# mitosis.net
KiCad netlist of a schematic drawn in Altium Designer
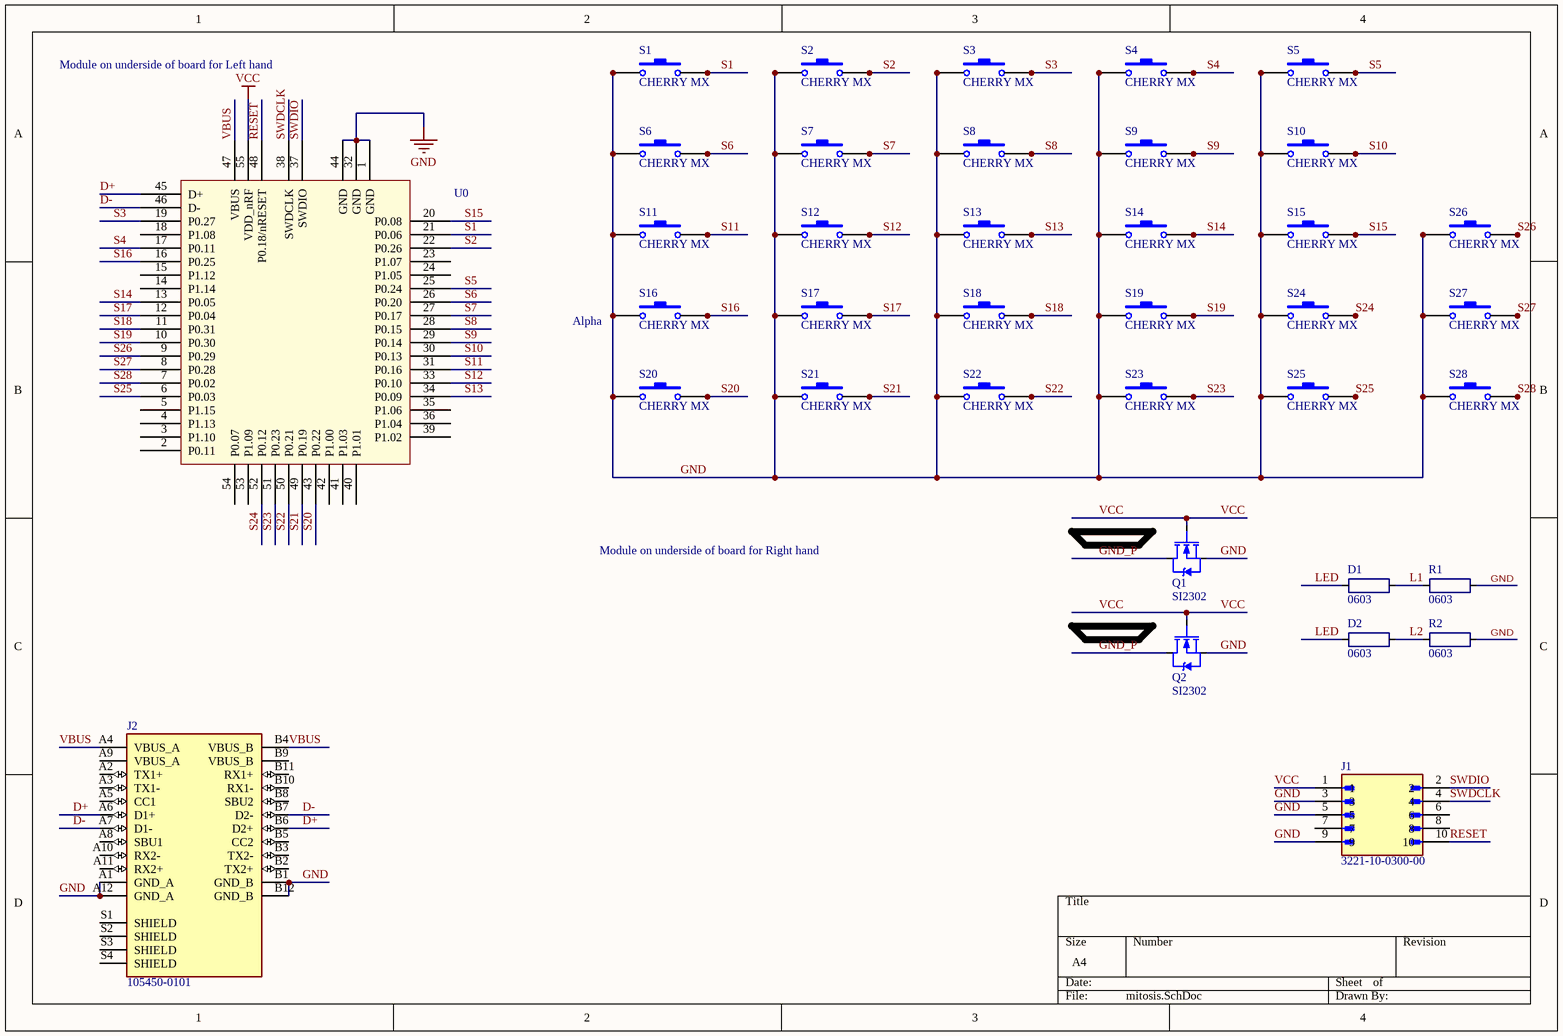
[diagram p0: mitosis.SchDoc]

(export (version "E")
  (design (tool "Eeschema 10.0.6"))
  (components
    (comp (ref "D1") (value "0603") (footprint "RESC2012X06N") (libsource (lib "SK") (part "0603")))
    (comp (ref "D2") (value "0603") (footprint "RESC2012X06N") (libsource (lib "SK") (part "0603")))
    (comp (ref "J1")
      (value "3221-10-0300-00")
      (footprint "mitosis:CNC_3221-10-0300-00")
      (description "Conn Shrouded Header HDR 10 POS 1.27mm Solder ST SMD T/R")
      (fields (field (name "MF") "CNC Tech") (field (name "MANUFACTURER PART NUMBER") "3221-10-0300-00-TR"))
      (libsource (lib "mitosis") (part "3221-10-0300-00"))
    )
    (comp (ref "J2")
      (value "105450-0101")
      (footprint "mitosis:MOLEX_105450-0101")
      (description "Conn USB 3.1 Type C F 24 POS Solder RA SMD 24 Terminal 1 Port USB 3.1 T/R")
      (fields (field (name "MANUFACTURER") "Molex"))
      (libsource (lib "mitosis") (part "105450-0101"))
    )
    (comp (ref "Q1")
      (value "SI2302")
      (footprint "SOT-23")
      (description "N-Channel Logic MOSFET")
      (fields (field (name "PUBLISHER") "Altium Limited"))
      (libsource (lib "SK") (part "SI2302"))
    )
    (comp (ref "Q2")
      (value "SI2302")
      (footprint "SOT-23")
      (description "N-Channel Logic MOSFET")
      (fields (field (name "PUBLISHER") "Altium Limited"))
      (libsource (lib "SK") (part "SI2302"))
    )
    (comp (ref "R1") (value "0603") (footprint "RESC2012X06N") (libsource (lib "SK") (part "0603")))
    (comp (ref "R2") (value "0603") (footprint "RESC2012X06N") (libsource (lib "SK") (part "0603")))
    (comp (ref "S1")
      (value "CHERRY MX")
      (footprint "cherry")
      (description "Switch")
      (fields (field (name "PUBLISHER") "Altium Limited"))
      (libsource (lib "SK") (part "CHERRY MX"))
    )
    (comp (ref "S2")
      (value "CHERRY MX")
      (footprint "cherry")
      (description "Switch")
      (fields (field (name "PUBLISHER") "Altium Limited"))
      (libsource (lib "SK") (part "CHERRY MX"))
    )
    (comp (ref "S3")
      (value "CHERRY MX")
      (footprint "cherry")
      (description "Switch")
      (fields (field (name "PUBLISHER") "Altium Limited"))
      (libsource (lib "SK") (part "CHERRY MX"))
    )
    (comp (ref "S4")
      (value "CHERRY MX")
      (footprint "cherry")
      (description "Switch")
      (fields (field (name "PUBLISHER") "Altium Limited"))
      (libsource (lib "SK") (part "CHERRY MX"))
    )
    (comp (ref "S5")
      (value "CHERRY MX")
      (footprint "cherry")
      (description "Switch")
      (fields (field (name "PUBLISHER") "Altium Limited"))
      (libsource (lib "SK") (part "CHERRY MX"))
    )
    (comp (ref "S6")
      (value "CHERRY MX")
      (footprint "cherry")
      (description "Switch")
      (fields (field (name "PUBLISHER") "Altium Limited"))
      (libsource (lib "SK") (part "CHERRY MX"))
    )
    (comp (ref "S7")
      (value "CHERRY MX")
      (footprint "cherry")
      (description "Switch")
      (fields (field (name "PUBLISHER") "Altium Limited"))
      (libsource (lib "SK") (part "CHERRY MX"))
    )
    (comp (ref "S8")
      (value "CHERRY MX")
      (footprint "cherry")
      (description "Switch")
      (fields (field (name "PUBLISHER") "Altium Limited"))
      (libsource (lib "SK") (part "CHERRY MX"))
    )
    (comp (ref "S9")
      (value "CHERRY MX")
      (footprint "cherry")
      (description "Switch")
      (fields (field (name "PUBLISHER") "Altium Limited"))
      (libsource (lib "SK") (part "CHERRY MX"))
    )
    (comp (ref "S10")
      (value "CHERRY MX")
      (footprint "cherry")
      (description "Switch")
      (fields (field (name "PUBLISHER") "Altium Limited"))
      (libsource (lib "SK") (part "CHERRY MX"))
    )
    (comp (ref "S11")
      (value "CHERRY MX")
      (footprint "cherry")
      (description "Switch")
      (fields (field (name "PUBLISHER") "Altium Limited"))
      (libsource (lib "SK") (part "CHERRY MX"))
    )
    (comp (ref "S12")
      (value "CHERRY MX")
      (footprint "cherry")
      (description "Switch")
      (fields (field (name "PUBLISHER") "Altium Limited"))
      (libsource (lib "SK") (part "CHERRY MX"))
    )
    (comp (ref "S13")
      (value "CHERRY MX")
      (footprint "cherry")
      (description "Switch")
      (fields (field (name "PUBLISHER") "Altium Limited"))
      (libsource (lib "SK") (part "CHERRY MX"))
    )
    (comp (ref "S14")
      (value "CHERRY MX")
      (footprint "cherry")
      (description "Switch")
      (fields (field (name "PUBLISHER") "Altium Limited"))
      (libsource (lib "SK") (part "CHERRY MX"))
    )
    (comp (ref "S15")
      (value "CHERRY MX")
      (footprint "cherry")
      (description "Switch")
      (fields (field (name "PUBLISHER") "Altium Limited"))
      (libsource (lib "SK") (part "CHERRY MX"))
    )
    (comp (ref "S16")
      (value "CHERRY MX")
      (footprint "cherry")
      (description "Switch")
      (fields (field (name "PUBLISHER") "Altium Limited"))
      (libsource (lib "SK") (part "CHERRY MX"))
    )
    (comp (ref "S17")
      (value "CHERRY MX")
      (footprint "cherry")
      (description "Switch")
      (fields (field (name "PUBLISHER") "Altium Limited"))
      (libsource (lib "SK") (part "CHERRY MX"))
    )
    (comp (ref "S18")
      (value "CHERRY MX")
      (footprint "cherry")
      (description "Switch")
      (fields (field (name "PUBLISHER") "Altium Limited"))
      (libsource (lib "SK") (part "CHERRY MX"))
    )
    (comp (ref "S19")
      (value "CHERRY MX")
      (footprint "cherry")
      (description "Switch")
      (fields (field (name "PUBLISHER") "Altium Limited"))
      (libsource (lib "SK") (part "CHERRY MX"))
    )
    (comp (ref "S20")
      (value "CHERRY MX")
      (footprint "cherry")
      (description "Switch")
      (fields (field (name "PUBLISHER") "Altium Limited"))
      (libsource (lib "SK") (part "CHERRY MX"))
    )
    (comp (ref "S21")
      (value "CHERRY MX")
      (footprint "cherry")
      (description "Switch")
      (fields (field (name "PUBLISHER") "Altium Limited"))
      (libsource (lib "SK") (part "CHERRY MX"))
    )
    (comp (ref "S22")
      (value "CHERRY MX")
      (footprint "cherry")
      (description "Switch")
      (fields (field (name "PUBLISHER") "Altium Limited"))
      (libsource (lib "SK") (part "CHERRY MX"))
    )
    (comp (ref "S23")
      (value "CHERRY MX")
      (footprint "cherry")
      (description "Switch")
      (fields (field (name "PUBLISHER") "Altium Limited"))
      (libsource (lib "SK") (part "CHERRY MX"))
    )
    (comp (ref "S24")
      (value "CHERRY MX")
      (footprint "cherry")
      (description "Switch")
      (fields (field (name "PUBLISHER") "Altium Limited"))
      (libsource (lib "mitosis") (part "CHERRY MX"))
    )
    (comp (ref "S25")
      (value "CHERRY MX")
      (footprint "cherry")
      (description "Switch")
      (fields (field (name "PUBLISHER") "Altium Limited"))
      (libsource (lib "mitosis") (part "CHERRY MX"))
    )
    (comp (ref "S26")
      (value "CHERRY MX")
      (footprint "cherry")
      (description "Switch")
      (fields (field (name "PUBLISHER") "Altium Limited"))
      (libsource (lib "mitosis") (part "CHERRY MX"))
    )
    (comp (ref "S27")
      (value "CHERRY MX")
      (footprint "cherry")
      (description "Switch")
      (fields (field (name "PUBLISHER") "Altium Limited"))
      (libsource (lib "mitosis") (part "CHERRY MX"))
    )
    (comp (ref "S28")
      (value "CHERRY MX")
      (footprint "cherry")
      (description "Switch")
      (fields (field (name "PUBLISHER") "Altium Limited"))
      (libsource (lib "mitosis") (part "CHERRY MX"))
    )
    (comp (ref "U0")
      (value "Core52840 (B)")
      (footprint "Core52840")
      (description "NRF52840 (B)")
      (libsource (lib "mitosis") (part "Core52840 (B)"))
    )
  )
  (nets
    (net (code "1") (name "/D+") (class "Default")
      (node (ref "J2") (pin "A6") (pinfunction "D1+_A6") (pintype "bidirectional"))
      (node (ref "J2") (pin "B6") (pinfunction "D2+_B6") (pintype "bidirectional"))
      (node (ref "U0") (pin "45") (pinfunction "D+_45") (pintype "passive"))
    )
    (net (code "2") (name "/D-") (class "Default")
      (node (ref "J2") (pin "A7") (pinfunction "D1-_A7") (pintype "bidirectional"))
      (node (ref "J2") (pin "B7") (pinfunction "D2-_B7") (pintype "bidirectional"))
      (node (ref "U0") (pin "46") (pinfunction "D-_46") (pintype "passive"))
    )
    (net (code "3") (name "/GND_P") (class "Default")
      (node (ref "Q1") (pin "3") (pinfunction "D_3") (pintype "passive"))
      (node (ref "Q2") (pin "3") (pinfunction "D_3") (pintype "passive"))
    )
    (net (code "4") (name "/L1") (class "Default")
      (node (ref "D1") (pin "1") (pinfunction "1_1") (pintype "passive"))
      (node (ref "R1") (pin "2") (pinfunction "2_2") (pintype "passive"))
    )
    (net (code "5") (name "/L2") (class "Default")
      (node (ref "D2") (pin "1") (pinfunction "1_1") (pintype "passive"))
      (node (ref "R2") (pin "2") (pinfunction "2_2") (pintype "passive"))
    )
    (net (code "6") (name "/LED") (class "Default")
      (node (ref "D1") (pin "2") (pinfunction "2_2") (pintype "passive"))
      (node (ref "D2") (pin "2") (pinfunction "2_2") (pintype "passive"))
    )
    (net (code "7") (name "/RESET") (class "Default")
      (node (ref "J1") (pin "10") (pinfunction "10_10") (pintype "passive"))
      (node (ref "U0") (pin "48") (pinfunction "P0.18/nRESET_48") (pintype "passive"))
    )
    (net (code "8") (name "/S1") (class "Default")
      (node (ref "S1") (pin "10") (pinfunction "10_10") (pintype "passive"))
      (node (ref "S1") (pin "12") (pinfunction "12_12") (pintype "passive"))
      (node (ref "S1") (pin "2") (pinfunction "2_2") (pintype "passive"))
      (node (ref "S1") (pin "4") (pinfunction "4_4") (pintype "passive"))
      (node (ref "S1") (pin "6") (pinfunction "6_6") (pintype "passive"))
      (node (ref "S1") (pin "8") (pinfunction "8_8") (pintype "passive"))
      (node (ref "U0") (pin "21") (pinfunction "P0.06_21") (pintype "passive"))
    )
    (net (code "9") (name "/S2") (class "Default")
      (node (ref "S2") (pin "10") (pinfunction "10_10") (pintype "passive"))
      (node (ref "S2") (pin "12") (pinfunction "12_12") (pintype "passive"))
      (node (ref "S2") (pin "2") (pinfunction "2_2") (pintype "passive"))
      (node (ref "S2") (pin "4") (pinfunction "4_4") (pintype "passive"))
      (node (ref "S2") (pin "6") (pinfunction "6_6") (pintype "passive"))
      (node (ref "S2") (pin "8") (pinfunction "8_8") (pintype "passive"))
      (node (ref "U0") (pin "22") (pinfunction "P0.26_22") (pintype "passive"))
    )
    (net (code "10") (name "/S3") (class "Default")
      (node (ref "S3") (pin "10") (pinfunction "10_10") (pintype "passive"))
      (node (ref "S3") (pin "12") (pinfunction "12_12") (pintype "passive"))
      (node (ref "S3") (pin "2") (pinfunction "2_2") (pintype "passive"))
      (node (ref "S3") (pin "4") (pinfunction "4_4") (pintype "passive"))
      (node (ref "S3") (pin "6") (pinfunction "6_6") (pintype "passive"))
      (node (ref "S3") (pin "8") (pinfunction "8_8") (pintype "passive"))
      (node (ref "U0") (pin "19") (pinfunction "P0.27_19") (pintype "passive"))
    )
    (net (code "11") (name "/S4") (class "Default")
      (node (ref "S4") (pin "10") (pinfunction "10_10") (pintype "passive"))
      (node (ref "S4") (pin "12") (pinfunction "12_12") (pintype "passive"))
      (node (ref "S4") (pin "2") (pinfunction "2_2") (pintype "passive"))
      (node (ref "S4") (pin "4") (pinfunction "4_4") (pintype "passive"))
      (node (ref "S4") (pin "6") (pinfunction "6_6") (pintype "passive"))
      (node (ref "S4") (pin "8") (pinfunction "8_8") (pintype "passive"))
      (node (ref "U0") (pin "17") (pinfunction "P0.11_17") (pintype "passive"))
    )
    (net (code "12") (name "/S5") (class "Default")
      (node (ref "S5") (pin "10") (pinfunction "10_10") (pintype "passive"))
      (node (ref "S5") (pin "12") (pinfunction "12_12") (pintype "passive"))
      (node (ref "S5") (pin "2") (pinfunction "2_2") (pintype "passive"))
      (node (ref "S5") (pin "4") (pinfunction "4_4") (pintype "passive"))
      (node (ref "S5") (pin "6") (pinfunction "6_6") (pintype "passive"))
      (node (ref "S5") (pin "8") (pinfunction "8_8") (pintype "passive"))
      (node (ref "U0") (pin "25") (pinfunction "P0.24_25") (pintype "passive"))
    )
    (net (code "13") (name "/S6") (class "Default")
      (node (ref "S6") (pin "10") (pinfunction "10_10") (pintype "passive"))
      (node (ref "S6") (pin "12") (pinfunction "12_12") (pintype "passive"))
      (node (ref "S6") (pin "2") (pinfunction "2_2") (pintype "passive"))
      (node (ref "S6") (pin "4") (pinfunction "4_4") (pintype "passive"))
      (node (ref "S6") (pin "6") (pinfunction "6_6") (pintype "passive"))
      (node (ref "S6") (pin "8") (pinfunction "8_8") (pintype "passive"))
      (node (ref "U0") (pin "26") (pinfunction "P0.20_26") (pintype "passive"))
    )
    (net (code "14") (name "/S7") (class "Default")
      (node (ref "S7") (pin "10") (pinfunction "10_10") (pintype "passive"))
      (node (ref "S7") (pin "12") (pinfunction "12_12") (pintype "passive"))
      (node (ref "S7") (pin "2") (pinfunction "2_2") (pintype "passive"))
      (node (ref "S7") (pin "4") (pinfunction "4_4") (pintype "passive"))
      (node (ref "S7") (pin "6") (pinfunction "6_6") (pintype "passive"))
      (node (ref "S7") (pin "8") (pinfunction "8_8") (pintype "passive"))
      (node (ref "U0") (pin "27") (pinfunction "P0.17_27") (pintype "passive"))
    )
    (net (code "15") (name "/S8") (class "Default")
      (node (ref "S8") (pin "10") (pinfunction "10_10") (pintype "passive"))
      (node (ref "S8") (pin "12") (pinfunction "12_12") (pintype "passive"))
      (node (ref "S8") (pin "2") (pinfunction "2_2") (pintype "passive"))
      (node (ref "S8") (pin "4") (pinfunction "4_4") (pintype "passive"))
      (node (ref "S8") (pin "6") (pinfunction "6_6") (pintype "passive"))
      (node (ref "S8") (pin "8") (pinfunction "8_8") (pintype "passive"))
      (node (ref "U0") (pin "28") (pinfunction "P0.15_28") (pintype "passive"))
    )
    (net (code "16") (name "/S9") (class "Default")
      (node (ref "S9") (pin "10") (pinfunction "10_10") (pintype "passive"))
      (node (ref "S9") (pin "12") (pinfunction "12_12") (pintype "passive"))
      (node (ref "S9") (pin "2") (pinfunction "2_2") (pintype "passive"))
      (node (ref "S9") (pin "4") (pinfunction "4_4") (pintype "passive"))
      (node (ref "S9") (pin "6") (pinfunction "6_6") (pintype "passive"))
      (node (ref "S9") (pin "8") (pinfunction "8_8") (pintype "passive"))
      (node (ref "U0") (pin "29") (pinfunction "P0.14_29") (pintype "passive"))
    )
    (net (code "17") (name "/S10") (class "Default")
      (node (ref "S10") (pin "10") (pinfunction "10_10") (pintype "passive"))
      (node (ref "S10") (pin "12") (pinfunction "12_12") (pintype "passive"))
      (node (ref "S10") (pin "2") (pinfunction "2_2") (pintype "passive"))
      (node (ref "S10") (pin "4") (pinfunction "4_4") (pintype "passive"))
      (node (ref "S10") (pin "6") (pinfunction "6_6") (pintype "passive"))
      (node (ref "S10") (pin "8") (pinfunction "8_8") (pintype "passive"))
      (node (ref "U0") (pin "30") (pinfunction "P0.13_30") (pintype "passive"))
    )
    (net (code "18") (name "/S11") (class "Default")
      (node (ref "S11") (pin "10") (pinfunction "10_10") (pintype "passive"))
      (node (ref "S11") (pin "12") (pinfunction "12_12") (pintype "passive"))
      (node (ref "S11") (pin "2") (pinfunction "2_2") (pintype "passive"))
      (node (ref "S11") (pin "4") (pinfunction "4_4") (pintype "passive"))
      (node (ref "S11") (pin "6") (pinfunction "6_6") (pintype "passive"))
      (node (ref "S11") (pin "8") (pinfunction "8_8") (pintype "passive"))
      (node (ref "U0") (pin "31") (pinfunction "P0.16_31") (pintype "passive"))
    )
    (net (code "19") (name "/S12") (class "Default")
      (node (ref "S12") (pin "10") (pinfunction "10_10") (pintype "passive"))
      (node (ref "S12") (pin "12") (pinfunction "12_12") (pintype "passive"))
      (node (ref "S12") (pin "2") (pinfunction "2_2") (pintype "passive"))
      (node (ref "S12") (pin "4") (pinfunction "4_4") (pintype "passive"))
      (node (ref "S12") (pin "6") (pinfunction "6_6") (pintype "passive"))
      (node (ref "S12") (pin "8") (pinfunction "8_8") (pintype "passive"))
      (node (ref "U0") (pin "33") (pinfunction "P0.10_33") (pintype "passive"))
    )
    (net (code "20") (name "/S13") (class "Default")
      (node (ref "S13") (pin "10") (pinfunction "10_10") (pintype "passive"))
      (node (ref "S13") (pin "12") (pinfunction "12_12") (pintype "passive"))
      (node (ref "S13") (pin "2") (pinfunction "2_2") (pintype "passive"))
      (node (ref "S13") (pin "4") (pinfunction "4_4") (pintype "passive"))
      (node (ref "S13") (pin "6") (pinfunction "6_6") (pintype "passive"))
      (node (ref "S13") (pin "8") (pinfunction "8_8") (pintype "passive"))
      (node (ref "U0") (pin "34") (pinfunction "P0.09_34") (pintype "passive"))
    )
    (net (code "21") (name "/S14") (class "Default")
      (node (ref "S14") (pin "10") (pinfunction "10_10") (pintype "passive"))
      (node (ref "S14") (pin "12") (pinfunction "12_12") (pintype "passive"))
      (node (ref "S14") (pin "2") (pinfunction "2_2") (pintype "passive"))
      (node (ref "S14") (pin "4") (pinfunction "4_4") (pintype "passive"))
      (node (ref "S14") (pin "6") (pinfunction "6_6") (pintype "passive"))
      (node (ref "S14") (pin "8") (pinfunction "8_8") (pintype "passive"))
      (node (ref "U0") (pin "13") (pinfunction "P0.05_13") (pintype "passive"))
    )
    (net (code "22") (name "/S15") (class "Default")
      (node (ref "S15") (pin "10") (pinfunction "10_10") (pintype "passive"))
      (node (ref "S15") (pin "12") (pinfunction "12_12") (pintype "passive"))
      (node (ref "S15") (pin "2") (pinfunction "2_2") (pintype "passive"))
      (node (ref "S15") (pin "4") (pinfunction "4_4") (pintype "passive"))
      (node (ref "S15") (pin "6") (pinfunction "6_6") (pintype "passive"))
      (node (ref "S15") (pin "8") (pinfunction "8_8") (pintype "passive"))
      (node (ref "U0") (pin "20") (pinfunction "P0.08_20") (pintype "passive"))
    )
    (net (code "23") (name "/S16") (class "Default")
      (node (ref "S16") (pin "10") (pinfunction "10_10") (pintype "passive"))
      (node (ref "S16") (pin "12") (pinfunction "12_12") (pintype "passive"))
      (node (ref "S16") (pin "2") (pinfunction "2_2") (pintype "passive"))
      (node (ref "S16") (pin "4") (pinfunction "4_4") (pintype "passive"))
      (node (ref "S16") (pin "6") (pinfunction "6_6") (pintype "passive"))
      (node (ref "S16") (pin "8") (pinfunction "8_8") (pintype "passive"))
      (node (ref "U0") (pin "16") (pinfunction "P0.25_16") (pintype "passive"))
    )
    (net (code "24") (name "/S17") (class "Default")
      (node (ref "S17") (pin "10") (pinfunction "10_10") (pintype "passive"))
      (node (ref "S17") (pin "12") (pinfunction "12_12") (pintype "passive"))
      (node (ref "S17") (pin "2") (pinfunction "2_2") (pintype "passive"))
      (node (ref "S17") (pin "4") (pinfunction "4_4") (pintype "passive"))
      (node (ref "S17") (pin "6") (pinfunction "6_6") (pintype "passive"))
      (node (ref "S17") (pin "8") (pinfunction "8_8") (pintype "passive"))
      (node (ref "U0") (pin "12") (pinfunction "P0.04_12") (pintype "passive"))
    )
    (net (code "25") (name "/S18") (class "Default")
      (node (ref "S18") (pin "10") (pinfunction "10_10") (pintype "passive"))
      (node (ref "S18") (pin "12") (pinfunction "12_12") (pintype "passive"))
      (node (ref "S18") (pin "2") (pinfunction "2_2") (pintype "passive"))
      (node (ref "S18") (pin "4") (pinfunction "4_4") (pintype "passive"))
      (node (ref "S18") (pin "6") (pinfunction "6_6") (pintype "passive"))
      (node (ref "S18") (pin "8") (pinfunction "8_8") (pintype "passive"))
      (node (ref "U0") (pin "11") (pinfunction "P0.31_11") (pintype "passive"))
    )
    (net (code "26") (name "/S19") (class "Default")
      (node (ref "S19") (pin "10") (pinfunction "10_10") (pintype "passive"))
      (node (ref "S19") (pin "12") (pinfunction "12_12") (pintype "passive"))
      (node (ref "S19") (pin "2") (pinfunction "2_2") (pintype "passive"))
      (node (ref "S19") (pin "4") (pinfunction "4_4") (pintype "passive"))
      (node (ref "S19") (pin "6") (pinfunction "6_6") (pintype "passive"))
      (node (ref "S19") (pin "8") (pinfunction "8_8") (pintype "passive"))
      (node (ref "U0") (pin "10") (pinfunction "P0.30_10") (pintype "passive"))
    )
    (net (code "27") (name "/S20") (class "Default")
      (node (ref "S20") (pin "10") (pinfunction "10_10") (pintype "passive"))
      (node (ref "S20") (pin "12") (pinfunction "12_12") (pintype "passive"))
      (node (ref "S20") (pin "2") (pinfunction "2_2") (pintype "passive"))
      (node (ref "S20") (pin "4") (pinfunction "4_4") (pintype "passive"))
      (node (ref "S20") (pin "6") (pinfunction "6_6") (pintype "passive"))
      (node (ref "S20") (pin "8") (pinfunction "8_8") (pintype "passive"))
      (node (ref "U0") (pin "43") (pinfunction "P0.22_43") (pintype "passive"))
    )
    (net (code "28") (name "/S21") (class "Default")
      (node (ref "S21") (pin "10") (pinfunction "10_10") (pintype "passive"))
      (node (ref "S21") (pin "12") (pinfunction "12_12") (pintype "passive"))
      (node (ref "S21") (pin "2") (pinfunction "2_2") (pintype "passive"))
      (node (ref "S21") (pin "4") (pinfunction "4_4") (pintype "passive"))
      (node (ref "S21") (pin "6") (pinfunction "6_6") (pintype "passive"))
      (node (ref "S21") (pin "8") (pinfunction "8_8") (pintype "passive"))
      (node (ref "U0") (pin "49") (pinfunction "P0.19_49") (pintype "passive"))
    )
    (net (code "29") (name "/S22") (class "Default")
      (node (ref "S22") (pin "10") (pinfunction "10_10") (pintype "passive"))
      (node (ref "S22") (pin "12") (pinfunction "12_12") (pintype "passive"))
      (node (ref "S22") (pin "2") (pinfunction "2_2") (pintype "passive"))
      (node (ref "S22") (pin "4") (pinfunction "4_4") (pintype "passive"))
      (node (ref "S22") (pin "6") (pinfunction "6_6") (pintype "passive"))
      (node (ref "S22") (pin "8") (pinfunction "8_8") (pintype "passive"))
      (node (ref "U0") (pin "50") (pinfunction "P0.21_50") (pintype "passive"))
    )
    (net (code "30") (name "/S23") (class "Default")
      (node (ref "S23") (pin "10") (pinfunction "10_10") (pintype "passive"))
      (node (ref "S23") (pin "12") (pinfunction "12_12") (pintype "passive"))
      (node (ref "S23") (pin "2") (pinfunction "2_2") (pintype "passive"))
      (node (ref "S23") (pin "4") (pinfunction "4_4") (pintype "passive"))
      (node (ref "S23") (pin "6") (pinfunction "6_6") (pintype "passive"))
      (node (ref "S23") (pin "8") (pinfunction "8_8") (pintype "passive"))
      (node (ref "U0") (pin "51") (pinfunction "P0.23_51") (pintype "passive"))
    )
    (net (code "31") (name "/S24") (class "Default")
      (node (ref "S24") (pin "10") (pinfunction "10_10") (pintype "passive"))
      (node (ref "S24") (pin "12") (pinfunction "12_12") (pintype "passive"))
      (node (ref "S24") (pin "2") (pinfunction "2_2") (pintype "passive"))
      (node (ref "S24") (pin "4") (pinfunction "4_4") (pintype "passive"))
      (node (ref "S24") (pin "6") (pinfunction "6_6") (pintype "passive"))
      (node (ref "S24") (pin "8") (pinfunction "8_8") (pintype "passive"))
      (node (ref "U0") (pin "52") (pinfunction "P0.12_52") (pintype "passive"))
    )
    (net (code "32") (name "/S25") (class "Default")
      (node (ref "S25") (pin "10") (pinfunction "10_10") (pintype "passive"))
      (node (ref "S25") (pin "12") (pinfunction "12_12") (pintype "passive"))
      (node (ref "S25") (pin "2") (pinfunction "2_2") (pintype "passive"))
      (node (ref "S25") (pin "4") (pinfunction "4_4") (pintype "passive"))
      (node (ref "S25") (pin "6") (pinfunction "6_6") (pintype "passive"))
      (node (ref "S25") (pin "8") (pinfunction "8_8") (pintype "passive"))
      (node (ref "U0") (pin "6") (pinfunction "P0.03_6") (pintype "passive"))
    )
    (net (code "33") (name "/S26") (class "Default")
      (node (ref "S26") (pin "10") (pinfunction "10_10") (pintype "passive"))
      (node (ref "S26") (pin "12") (pinfunction "12_12") (pintype "passive"))
      (node (ref "S26") (pin "2") (pinfunction "2_2") (pintype "passive"))
      (node (ref "S26") (pin "4") (pinfunction "4_4") (pintype "passive"))
      (node (ref "S26") (pin "6") (pinfunction "6_6") (pintype "passive"))
      (node (ref "S26") (pin "8") (pinfunction "8_8") (pintype "passive"))
      (node (ref "U0") (pin "9") (pinfunction "P0.29_9") (pintype "passive"))
    )
    (net (code "34") (name "/S27") (class "Default")
      (node (ref "S27") (pin "10") (pinfunction "10_10") (pintype "passive"))
      (node (ref "S27") (pin "12") (pinfunction "12_12") (pintype "passive"))
      (node (ref "S27") (pin "2") (pinfunction "2_2") (pintype "passive"))
      (node (ref "S27") (pin "4") (pinfunction "4_4") (pintype "passive"))
      (node (ref "S27") (pin "6") (pinfunction "6_6") (pintype "passive"))
      (node (ref "S27") (pin "8") (pinfunction "8_8") (pintype "passive"))
      (node (ref "U0") (pin "8") (pinfunction "P0.28_8") (pintype "passive"))
    )
    (net (code "35") (name "/S28") (class "Default")
      (node (ref "S28") (pin "10") (pinfunction "10_10") (pintype "passive"))
      (node (ref "S28") (pin "12") (pinfunction "12_12") (pintype "passive"))
      (node (ref "S28") (pin "2") (pinfunction "2_2") (pintype "passive"))
      (node (ref "S28") (pin "4") (pinfunction "4_4") (pintype "passive"))
      (node (ref "S28") (pin "6") (pinfunction "6_6") (pintype "passive"))
      (node (ref "S28") (pin "8") (pinfunction "8_8") (pintype "passive"))
      (node (ref "U0") (pin "7") (pinfunction "P0.02_7") (pintype "passive"))
    )
    (net (code "36") (name "/SWDCLK") (class "Default")
      (node (ref "J1") (pin "4") (pinfunction "4_4") (pintype "passive"))
      (node (ref "U0") (pin "38") (pinfunction "SWDCLK_38") (pintype "passive"))
    )
    (net (code "37") (name "/SWDIO") (class "Default")
      (node (ref "J1") (pin "2") (pinfunction "2_2") (pintype "passive"))
      (node (ref "U0") (pin "37") (pinfunction "SWDIO_37") (pintype "passive"))
    )
    (net (code "38") (name "/VBUS") (class "Default")
      (node (ref "J2") (pin "A4") (pinfunction "VBUS_A_A4") (pintype "power_in"))
      (node (ref "J2") (pin "B4") (pinfunction "VBUS_B_B4") (pintype "power_in"))
      (node (ref "U0") (pin "47") (pinfunction "VBUS_47") (pintype "passive"))
    )
    (net (code "39") (name "GND") (class "Default")
      (node (ref "J1") (pin "3") (pinfunction "3_3") (pintype "passive"))
      (node (ref "J1") (pin "5") (pinfunction "5_5") (pintype "passive"))
      (node (ref "J1") (pin "9") (pinfunction "9_9") (pintype "passive"))
      (node (ref "J2") (pin "A1") (pinfunction "GND_A_A1") (pintype "power_in"))
      (node (ref "J2") (pin "A12") (pinfunction "GND_A_A12") (pintype "power_in"))
      (node (ref "J2") (pin "B1") (pinfunction "GND_B_B1") (pintype "power_in"))
      (node (ref "J2") (pin "B12") (pinfunction "GND_B_B12") (pintype "power_in"))
      (node (ref "Q1") (pin "2") (pinfunction "S_2") (pintype "passive"))
      (node (ref "Q2") (pin "2") (pinfunction "S_2") (pintype "passive"))
      (node (ref "R1") (pin "1") (pinfunction "1_1") (pintype "passive"))
      (node (ref "R2") (pin "1") (pinfunction "1_1") (pintype "passive"))
      (node (ref "S1") (pin "1") (pinfunction "1_1") (pintype "passive"))
      (node (ref "S1") (pin "11") (pinfunction "11_11") (pintype "passive"))
      (node (ref "S1") (pin "3") (pinfunction "3_3") (pintype "passive"))
      (node (ref "S1") (pin "5") (pinfunction "5_5") (pintype "passive"))
      (node (ref "S1") (pin "7") (pinfunction "7_7") (pintype "passive"))
      (node (ref "S1") (pin "9") (pinfunction "9_9") (pintype "passive"))
      (node (ref "S10") (pin "1") (pinfunction "1_1") (pintype "passive"))
      (node (ref "S10") (pin "11") (pinfunction "11_11") (pintype "passive"))
      (node (ref "S10") (pin "3") (pinfunction "3_3") (pintype "passive"))
      (node (ref "S10") (pin "5") (pinfunction "5_5") (pintype "passive"))
      (node (ref "S10") (pin "7") (pinfunction "7_7") (pintype "passive"))
      (node (ref "S10") (pin "9") (pinfunction "9_9") (pintype "passive"))
      (node (ref "S11") (pin "1") (pinfunction "1_1") (pintype "passive"))
      (node (ref "S11") (pin "11") (pinfunction "11_11") (pintype "passive"))
      (node (ref "S11") (pin "3") (pinfunction "3_3") (pintype "passive"))
      (node (ref "S11") (pin "5") (pinfunction "5_5") (pintype "passive"))
      (node (ref "S11") (pin "7") (pinfunction "7_7") (pintype "passive"))
      (node (ref "S11") (pin "9") (pinfunction "9_9") (pintype "passive"))
      (node (ref "S12") (pin "1") (pinfunction "1_1") (pintype "passive"))
      (node (ref "S12") (pin "11") (pinfunction "11_11") (pintype "passive"))
      (node (ref "S12") (pin "3") (pinfunction "3_3") (pintype "passive"))
      (node (ref "S12") (pin "5") (pinfunction "5_5") (pintype "passive"))
      (node (ref "S12") (pin "7") (pinfunction "7_7") (pintype "passive"))
      (node (ref "S12") (pin "9") (pinfunction "9_9") (pintype "passive"))
      (node (ref "S13") (pin "1") (pinfunction "1_1") (pintype "passive"))
      (node (ref "S13") (pin "11") (pinfunction "11_11") (pintype "passive"))
      (node (ref "S13") (pin "3") (pinfunction "3_3") (pintype "passive"))
      (node (ref "S13") (pin "5") (pinfunction "5_5") (pintype "passive"))
      (node (ref "S13") (pin "7") (pinfunction "7_7") (pintype "passive"))
      (node (ref "S13") (pin "9") (pinfunction "9_9") (pintype "passive"))
      (node (ref "S14") (pin "1") (pinfunction "1_1") (pintype "passive"))
      (node (ref "S14") (pin "11") (pinfunction "11_11") (pintype "passive"))
      (node (ref "S14") (pin "3") (pinfunction "3_3") (pintype "passive"))
      (node (ref "S14") (pin "5") (pinfunction "5_5") (pintype "passive"))
      (node (ref "S14") (pin "7") (pinfunction "7_7") (pintype "passive"))
      (node (ref "S14") (pin "9") (pinfunction "9_9") (pintype "passive"))
      (node (ref "S15") (pin "1") (pinfunction "1_1") (pintype "passive"))
      (node (ref "S15") (pin "11") (pinfunction "11_11") (pintype "passive"))
      (node (ref "S15") (pin "3") (pinfunction "3_3") (pintype "passive"))
      (node (ref "S15") (pin "5") (pinfunction "5_5") (pintype "passive"))
      (node (ref "S15") (pin "7") (pinfunction "7_7") (pintype "passive"))
      (node (ref "S15") (pin "9") (pinfunction "9_9") (pintype "passive"))
      (node (ref "S16") (pin "1") (pinfunction "1_1") (pintype "passive"))
      (node (ref "S16") (pin "11") (pinfunction "11_11") (pintype "passive"))
      (node (ref "S16") (pin "3") (pinfunction "3_3") (pintype "passive"))
      (node (ref "S16") (pin "5") (pinfunction "5_5") (pintype "passive"))
      (node (ref "S16") (pin "7") (pinfunction "7_7") (pintype "passive"))
      (node (ref "S16") (pin "9") (pinfunction "9_9") (pintype "passive"))
      (node (ref "S17") (pin "1") (pinfunction "1_1") (pintype "passive"))
      (node (ref "S17") (pin "11") (pinfunction "11_11") (pintype "passive"))
      (node (ref "S17") (pin "3") (pinfunction "3_3") (pintype "passive"))
      (node (ref "S17") (pin "5") (pinfunction "5_5") (pintype "passive"))
      (node (ref "S17") (pin "7") (pinfunction "7_7") (pintype "passive"))
      (node (ref "S17") (pin "9") (pinfunction "9_9") (pintype "passive"))
      (node (ref "S18") (pin "1") (pinfunction "1_1") (pintype "passive"))
      (node (ref "S18") (pin "11") (pinfunction "11_11") (pintype "passive"))
      (node (ref "S18") (pin "3") (pinfunction "3_3") (pintype "passive"))
      (node (ref "S18") (pin "5") (pinfunction "5_5") (pintype "passive"))
      (node (ref "S18") (pin "7") (pinfunction "7_7") (pintype "passive"))
      (node (ref "S18") (pin "9") (pinfunction "9_9") (pintype "passive"))
      (node (ref "S19") (pin "1") (pinfunction "1_1") (pintype "passive"))
      (node (ref "S19") (pin "11") (pinfunction "11_11") (pintype "passive"))
      (node (ref "S19") (pin "3") (pinfunction "3_3") (pintype "passive"))
      (node (ref "S19") (pin "5") (pinfunction "5_5") (pintype "passive"))
      (node (ref "S19") (pin "7") (pinfunction "7_7") (pintype "passive"))
      (node (ref "S19") (pin "9") (pinfunction "9_9") (pintype "passive"))
      (node (ref "S2") (pin "1") (pinfunction "1_1") (pintype "passive"))
      (node (ref "S2") (pin "11") (pinfunction "11_11") (pintype "passive"))
      (node (ref "S2") (pin "3") (pinfunction "3_3") (pintype "passive"))
      (node (ref "S2") (pin "5") (pinfunction "5_5") (pintype "passive"))
      (node (ref "S2") (pin "7") (pinfunction "7_7") (pintype "passive"))
      (node (ref "S2") (pin "9") (pinfunction "9_9") (pintype "passive"))
      (node (ref "S20") (pin "1") (pinfunction "1_1") (pintype "passive"))
      (node (ref "S20") (pin "11") (pinfunction "11_11") (pintype "passive"))
      (node (ref "S20") (pin "3") (pinfunction "3_3") (pintype "passive"))
      (node (ref "S20") (pin "5") (pinfunction "5_5") (pintype "passive"))
      (node (ref "S20") (pin "7") (pinfunction "7_7") (pintype "passive"))
      (node (ref "S20") (pin "9") (pinfunction "9_9") (pintype "passive"))
      (node (ref "S21") (pin "1") (pinfunction "1_1") (pintype "passive"))
      (node (ref "S21") (pin "11") (pinfunction "11_11") (pintype "passive"))
      (node (ref "S21") (pin "3") (pinfunction "3_3") (pintype "passive"))
      (node (ref "S21") (pin "5") (pinfunction "5_5") (pintype "passive"))
      (node (ref "S21") (pin "7") (pinfunction "7_7") (pintype "passive"))
      (node (ref "S21") (pin "9") (pinfunction "9_9") (pintype "passive"))
      (node (ref "S22") (pin "1") (pinfunction "1_1") (pintype "passive"))
      (node (ref "S22") (pin "11") (pinfunction "11_11") (pintype "passive"))
      (node (ref "S22") (pin "3") (pinfunction "3_3") (pintype "passive"))
      (node (ref "S22") (pin "5") (pinfunction "5_5") (pintype "passive"))
      (node (ref "S22") (pin "7") (pinfunction "7_7") (pintype "passive"))
      (node (ref "S22") (pin "9") (pinfunction "9_9") (pintype "passive"))
      (node (ref "S23") (pin "1") (pinfunction "1_1") (pintype "passive"))
      (node (ref "S23") (pin "11") (pinfunction "11_11") (pintype "passive"))
      (node (ref "S23") (pin "3") (pinfunction "3_3") (pintype "passive"))
      (node (ref "S23") (pin "5") (pinfunction "5_5") (pintype "passive"))
      (node (ref "S23") (pin "7") (pinfunction "7_7") (pintype "passive"))
      (node (ref "S23") (pin "9") (pinfunction "9_9") (pintype "passive"))
      (node (ref "S24") (pin "1") (pinfunction "1_1") (pintype "passive"))
      (node (ref "S24") (pin "11") (pinfunction "11_11") (pintype "passive"))
      (node (ref "S24") (pin "3") (pinfunction "3_3") (pintype "passive"))
      (node (ref "S24") (pin "5") (pinfunction "5_5") (pintype "passive"))
      (node (ref "S24") (pin "7") (pinfunction "7_7") (pintype "passive"))
      (node (ref "S24") (pin "9") (pinfunction "9_9") (pintype "passive"))
      (node (ref "S25") (pin "1") (pinfunction "1_1") (pintype "passive"))
      (node (ref "S25") (pin "11") (pinfunction "11_11") (pintype "passive"))
      (node (ref "S25") (pin "3") (pinfunction "3_3") (pintype "passive"))
      (node (ref "S25") (pin "5") (pinfunction "5_5") (pintype "passive"))
      (node (ref "S25") (pin "7") (pinfunction "7_7") (pintype "passive"))
      (node (ref "S25") (pin "9") (pinfunction "9_9") (pintype "passive"))
      (node (ref "S26") (pin "1") (pinfunction "1_1") (pintype "passive"))
      (node (ref "S26") (pin "11") (pinfunction "11_11") (pintype "passive"))
      (node (ref "S26") (pin "3") (pinfunction "3_3") (pintype "passive"))
      (node (ref "S26") (pin "5") (pinfunction "5_5") (pintype "passive"))
      (node (ref "S26") (pin "7") (pinfunction "7_7") (pintype "passive"))
      (node (ref "S26") (pin "9") (pinfunction "9_9") (pintype "passive"))
      (node (ref "S27") (pin "1") (pinfunction "1_1") (pintype "passive"))
      (node (ref "S27") (pin "11") (pinfunction "11_11") (pintype "passive"))
      (node (ref "S27") (pin "3") (pinfunction "3_3") (pintype "passive"))
      (node (ref "S27") (pin "5") (pinfunction "5_5") (pintype "passive"))
      (node (ref "S27") (pin "7") (pinfunction "7_7") (pintype "passive"))
      (node (ref "S27") (pin "9") (pinfunction "9_9") (pintype "passive"))
      (node (ref "S28") (pin "1") (pinfunction "1_1") (pintype "passive"))
      (node (ref "S28") (pin "11") (pinfunction "11_11") (pintype "passive"))
      (node (ref "S28") (pin "3") (pinfunction "3_3") (pintype "passive"))
      (node (ref "S28") (pin "5") (pinfunction "5_5") (pintype "passive"))
      (node (ref "S28") (pin "7") (pinfunction "7_7") (pintype "passive"))
      (node (ref "S28") (pin "9") (pinfunction "9_9") (pintype "passive"))
      (node (ref "S3") (pin "1") (pinfunction "1_1") (pintype "passive"))
      (node (ref "S3") (pin "11") (pinfunction "11_11") (pintype "passive"))
      (node (ref "S3") (pin "3") (pinfunction "3_3") (pintype "passive"))
      (node (ref "S3") (pin "5") (pinfunction "5_5") (pintype "passive"))
      (node (ref "S3") (pin "7") (pinfunction "7_7") (pintype "passive"))
      (node (ref "S3") (pin "9") (pinfunction "9_9") (pintype "passive"))
      (node (ref "S4") (pin "1") (pinfunction "1_1") (pintype "passive"))
      (node (ref "S4") (pin "11") (pinfunction "11_11") (pintype "passive"))
      (node (ref "S4") (pin "3") (pinfunction "3_3") (pintype "passive"))
      (node (ref "S4") (pin "5") (pinfunction "5_5") (pintype "passive"))
      (node (ref "S4") (pin "7") (pinfunction "7_7") (pintype "passive"))
      (node (ref "S4") (pin "9") (pinfunction "9_9") (pintype "passive"))
      (node (ref "S5") (pin "1") (pinfunction "1_1") (pintype "passive"))
      (node (ref "S5") (pin "11") (pinfunction "11_11") (pintype "passive"))
      (node (ref "S5") (pin "3") (pinfunction "3_3") (pintype "passive"))
      (node (ref "S5") (pin "5") (pinfunction "5_5") (pintype "passive"))
      (node (ref "S5") (pin "7") (pinfunction "7_7") (pintype "passive"))
      (node (ref "S5") (pin "9") (pinfunction "9_9") (pintype "passive"))
      (node (ref "S6") (pin "1") (pinfunction "1_1") (pintype "passive"))
      (node (ref "S6") (pin "11") (pinfunction "11_11") (pintype "passive"))
      (node (ref "S6") (pin "3") (pinfunction "3_3") (pintype "passive"))
      (node (ref "S6") (pin "5") (pinfunction "5_5") (pintype "passive"))
      (node (ref "S6") (pin "7") (pinfunction "7_7") (pintype "passive"))
      (node (ref "S6") (pin "9") (pinfunction "9_9") (pintype "passive"))
      (node (ref "S7") (pin "1") (pinfunction "1_1") (pintype "passive"))
      (node (ref "S7") (pin "11") (pinfunction "11_11") (pintype "passive"))
      (node (ref "S7") (pin "3") (pinfunction "3_3") (pintype "passive"))
      (node (ref "S7") (pin "5") (pinfunction "5_5") (pintype "passive"))
      (node (ref "S7") (pin "7") (pinfunction "7_7") (pintype "passive"))
      (node (ref "S7") (pin "9") (pinfunction "9_9") (pintype "passive"))
      (node (ref "S8") (pin "1") (pinfunction "1_1") (pintype "passive"))
      (node (ref "S8") (pin "11") (pinfunction "11_11") (pintype "passive"))
      (node (ref "S8") (pin "3") (pinfunction "3_3") (pintype "passive"))
      (node (ref "S8") (pin "5") (pinfunction "5_5") (pintype "passive"))
      (node (ref "S8") (pin "7") (pinfunction "7_7") (pintype "passive"))
      (node (ref "S8") (pin "9") (pinfunction "9_9") (pintype "passive"))
      (node (ref "S9") (pin "1") (pinfunction "1_1") (pintype "passive"))
      (node (ref "S9") (pin "11") (pinfunction "11_11") (pintype "passive"))
      (node (ref "S9") (pin "3") (pinfunction "3_3") (pintype "passive"))
      (node (ref "S9") (pin "5") (pinfunction "5_5") (pintype "passive"))
      (node (ref "S9") (pin "7") (pinfunction "7_7") (pintype "passive"))
      (node (ref "S9") (pin "9") (pinfunction "9_9") (pintype "passive"))
      (node (ref "U0") (pin "1") (pinfunction "GND_1") (pintype "passive"))
      (node (ref "U0") (pin "32") (pinfunction "GND_32") (pintype "passive"))
      (node (ref "U0") (pin "44") (pinfunction "GND_44") (pintype "passive"))
    )
    (net (code "40") (name "VCC") (class "Default")
      (node (ref "J1") (pin "1") (pinfunction "1_1") (pintype "passive"))
      (node (ref "Q1") (pin "1") (pinfunction "G_1") (pintype "passive"))
      (node (ref "Q2") (pin "1") (pinfunction "G_1") (pintype "passive"))
      (node (ref "U0") (pin "55") (pinfunction "VDD_nRF_55") (pintype "passive"))
    )
    (net (code "41") (name "unconnected-(J1-Pad6)") (class "Default")
      (node (ref "J1") (pin "6") (pinfunction "6_6") (pintype "passive"))
    )
    (net (code "42") (name "unconnected-(J1-Pad7)") (class "Default")
      (node (ref "J1") (pin "7") (pinfunction "7_7") (pintype "passive"))
    )
    (net (code "43") (name "unconnected-(J1-Pad8)") (class "Default")
      (node (ref "J1") (pin "8") (pinfunction "8_8") (pintype "passive"))
    )
    (net (code "44") (name "unconnected-(J2-CC1-PadA5)") (class "Default")
      (node (ref "J2") (pin "A5") (pinfunction "CC1_A5") (pintype "bidirectional"))
    )
    (net (code "45") (name "unconnected-(J2-CC2-PadB5)") (class "Default")
      (node (ref "J2") (pin "B5") (pinfunction "CC2_B5") (pintype "bidirectional"))
    )
    (net (code "46") (name "unconnected-(J2-RX1+-PadB11)") (class "Default")
      (node (ref "J2") (pin "B11") (pinfunction "RX1+_B11") (pintype "bidirectional"))
    )
    (net (code "47") (name "unconnected-(J2-RX1--PadB10)") (class "Default")
      (node (ref "J2") (pin "B10") (pinfunction "RX1-_B10") (pintype "bidirectional"))
    )
    (net (code "48") (name "unconnected-(J2-RX2+-PadA11)") (class "Default")
      (node (ref "J2") (pin "A11") (pinfunction "RX2+_A11") (pintype "bidirectional"))
    )
    (net (code "49") (name "unconnected-(J2-RX2--PadA10)") (class "Default")
      (node (ref "J2") (pin "A10") (pinfunction "RX2-_A10") (pintype "bidirectional"))
    )
    (net (code "50") (name "unconnected-(J2-SBU1-PadA8)") (class "Default")
      (node (ref "J2") (pin "A8") (pinfunction "SBU1_A8") (pintype "bidirectional"))
    )
    (net (code "51") (name "unconnected-(J2-SBU2-PadB8)") (class "Default")
      (node (ref "J2") (pin "B8") (pinfunction "SBU2_B8") (pintype "bidirectional"))
    )
    (net (code "52") (name "unconnected-(J2-SHIELD-PadS1)") (class "Default")
      (node (ref "J2") (pin "S1") (pinfunction "SHIELD_S1") (pintype "passive"))
    )
    (net (code "53") (name "unconnected-(J2-SHIELD-PadS2)") (class "Default")
      (node (ref "J2") (pin "S2") (pinfunction "SHIELD_S2") (pintype "passive"))
    )
    (net (code "54") (name "unconnected-(J2-SHIELD-PadS3)") (class "Default")
      (node (ref "J2") (pin "S3") (pinfunction "SHIELD_S3") (pintype "passive"))
    )
    (net (code "55") (name "unconnected-(J2-SHIELD-PadS4)") (class "Default")
      (node (ref "J2") (pin "S4") (pinfunction "SHIELD_S4") (pintype "passive"))
    )
    (net (code "56") (name "unconnected-(J2-TX1+-PadA2)") (class "Default")
      (node (ref "J2") (pin "A2") (pinfunction "TX1+_A2") (pintype "bidirectional"))
    )
    (net (code "57") (name "unconnected-(J2-TX1--PadA3)") (class "Default")
      (node (ref "J2") (pin "A3") (pinfunction "TX1-_A3") (pintype "bidirectional"))
    )
    (net (code "58") (name "unconnected-(J2-TX2+-PadB2)") (class "Default")
      (node (ref "J2") (pin "B2") (pinfunction "TX2+_B2") (pintype "bidirectional"))
    )
    (net (code "59") (name "unconnected-(J2-TX2--PadB3)") (class "Default")
      (node (ref "J2") (pin "B3") (pinfunction "TX2-_B3") (pintype "bidirectional"))
    )
    (net (code "60") (name "unconnected-(J2-VBUS_A-PadA9)") (class "Default")
      (node (ref "J2") (pin "A9") (pinfunction "VBUS_A_A9") (pintype "power_in"))
    )
    (net (code "61") (name "unconnected-(J2-VBUS_B-PadB9)") (class "Default")
      (node (ref "J2") (pin "B9") (pinfunction "VBUS_B_B9") (pintype "power_in"))
    )
    (net (code "62") (name "unconnected-(U0-P0.07-Pad54)") (class "Default")
      (node (ref "U0") (pin "54") (pinfunction "P0.07_54") (pintype "passive"))
    )
    (net (code "63") (name "unconnected-(U0-P0.11-Pad2)") (class "Default")
      (node (ref "U0") (pin "2") (pinfunction "P0.11_2") (pintype "passive"))
    )
    (net (code "64") (name "unconnected-(U0-P1.00-Pad42)") (class "Default")
      (node (ref "U0") (pin "42") (pinfunction "P1.00_42") (pintype "passive"))
    )
    (net (code "65") (name "unconnected-(U0-P1.01-Pad40)") (class "Default")
      (node (ref "U0") (pin "40") (pinfunction "P1.01_40") (pintype "passive"))
    )
    (net (code "66") (name "unconnected-(U0-P1.02-Pad39)") (class "Default")
      (node (ref "U0") (pin "39") (pinfunction "P1.02_39") (pintype "passive"))
    )
    (net (code "67") (name "unconnected-(U0-P1.03-Pad41)") (class "Default")
      (node (ref "U0") (pin "41") (pinfunction "P1.03_41") (pintype "passive"))
    )
    (net (code "68") (name "unconnected-(U0-P1.04-Pad36)") (class "Default")
      (node (ref "U0") (pin "36") (pinfunction "P1.04_36") (pintype "passive"))
    )
    (net (code "69") (name "unconnected-(U0-P1.05-Pad24)") (class "Default")
      (node (ref "U0") (pin "24") (pinfunction "P1.05_24") (pintype "passive"))
    )
    (net (code "70") (name "unconnected-(U0-P1.06-Pad35)") (class "Default")
      (node (ref "U0") (pin "35") (pinfunction "P1.06_35") (pintype "passive"))
    )
    (net (code "71") (name "unconnected-(U0-P1.07-Pad23)") (class "Default")
      (node (ref "U0") (pin "23") (pinfunction "P1.07_23") (pintype "passive"))
    )
    (net (code "72") (name "unconnected-(U0-P1.08-Pad18)") (class "Default")
      (node (ref "U0") (pin "18") (pinfunction "P1.08_18") (pintype "passive"))
    )
    (net (code "73") (name "unconnected-(U0-P1.09-Pad53)") (class "Default")
      (node (ref "U0") (pin "53") (pinfunction "P1.09_53") (pintype "passive"))
    )
    (net (code "74") (name "unconnected-(U0-P1.10-Pad3)") (class "Default")
      (node (ref "U0") (pin "3") (pinfunction "P1.10_3") (pintype "passive"))
    )
    (net (code "75") (name "unconnected-(U0-P1.12-Pad15)") (class "Default")
      (node (ref "U0") (pin "15") (pinfunction "P1.12_15") (pintype "passive"))
    )
    (net (code "76") (name "unconnected-(U0-P1.13-Pad4)") (class "Default")
      (node (ref "U0") (pin "4") (pinfunction "P1.13_4") (pintype "passive"))
    )
    (net (code "77") (name "unconnected-(U0-P1.14-Pad14)") (class "Default")
      (node (ref "U0") (pin "14") (pinfunction "P1.14_14") (pintype "passive"))
    )
    (net (code "78") (name "unconnected-(U0-P1.15-Pad5)") (class "Default")
      (node (ref "U0") (pin "5") (pinfunction "P1.15_5") (pintype "passive"))
    )
  )
)
